# RX.net
KiCad netlist of a schematic drawn in Altium Designer
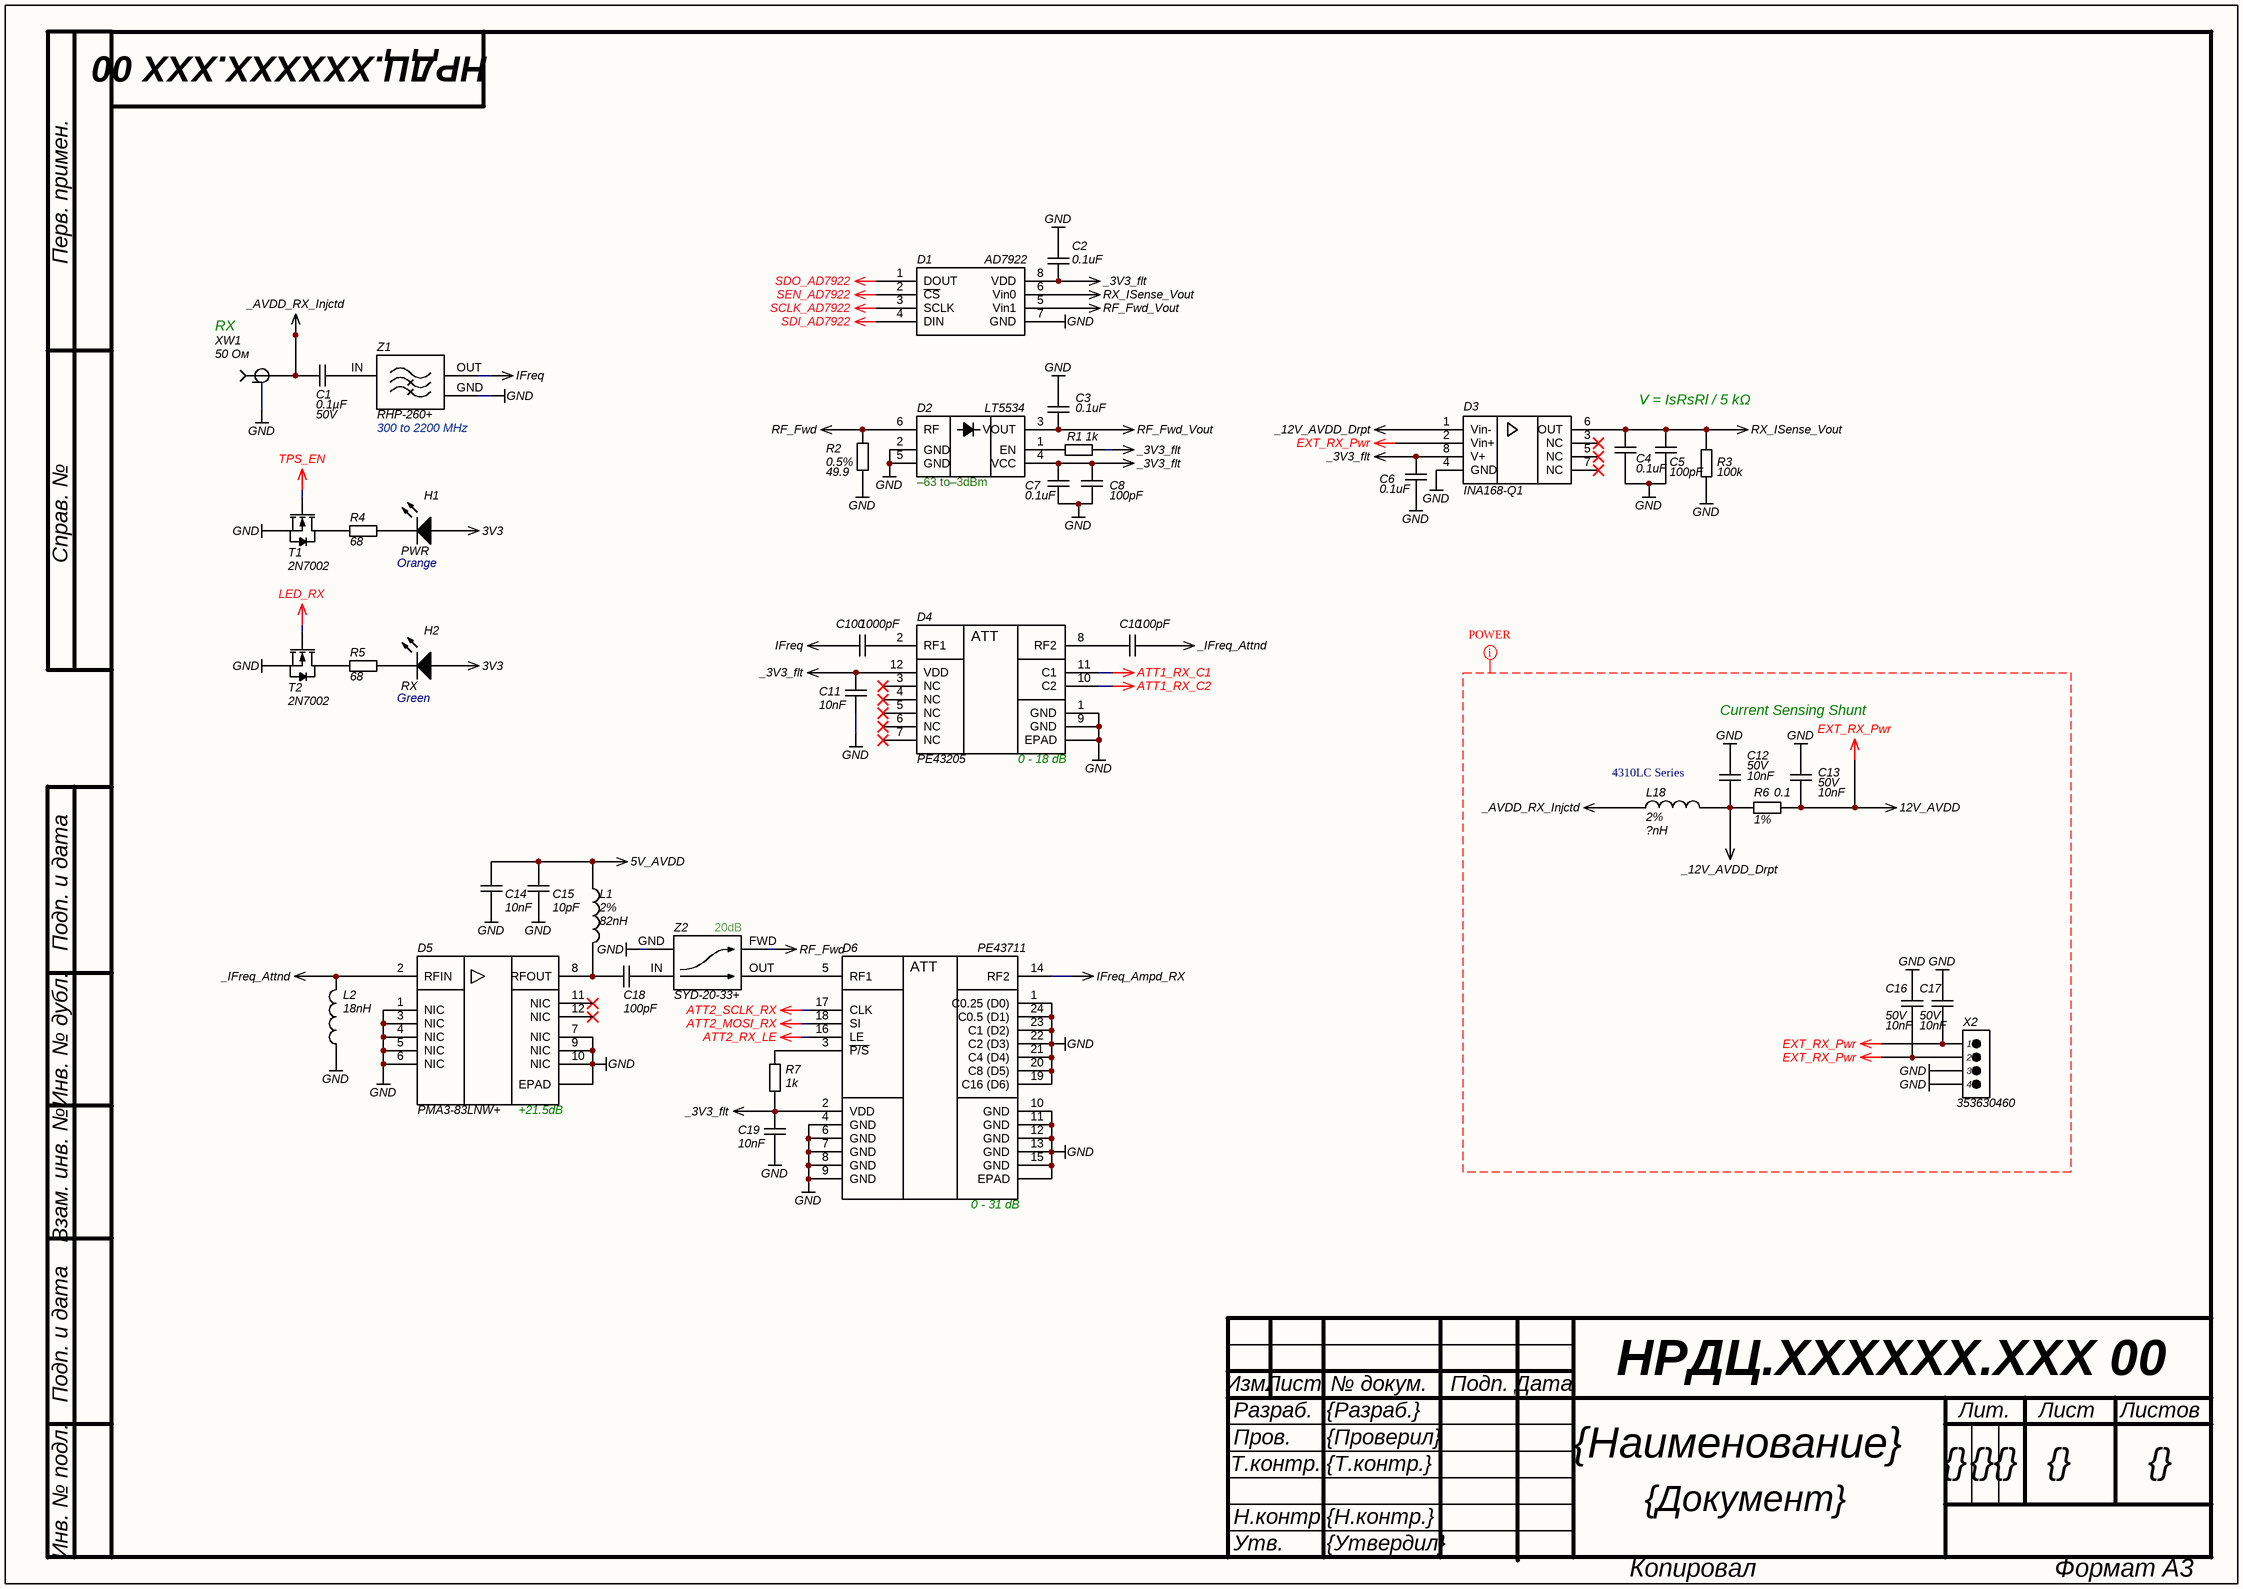
[diagram p0: RX.SchDoc]

(export (version "E")
  (design (tool "Eeschema 10.0.6"))
  (components
    (comp (ref "C1")
      (value "0.1µF")
      (footprint "C1206")
      (description "SMD Capacitor")
      (fields
        (field (name "MANUFACTURER") "Murata")
        (field (name "TOLERANCE") "5%")
        (field (name "VOLTAGE") "50V")
      )
      (libsource (lib "Kintex_SDR") (part "CAP"))
    )
    (comp (ref "C2")
      (value "0.1uF")
      (footprint "C0402")
      (description "SMD Capacitor")
      (fields (field (name "MANUFACTURER") "Murata") (field (name "TOLERANCE") "10%"))
      (libsource (lib "Kintex_SDR") (part "CAP"))
    )
    (comp (ref "C3")
      (value "0.1uF")
      (footprint "C0402")
      (description "SMD Capacitor")
      (fields (field (name "MANUFACTURER") "Murata") (field (name "TOLERANCE") "10%"))
      (libsource (lib "Kintex_SDR") (part "CAP"))
    )
    (comp (ref "C4")
      (value "0.1uF")
      (footprint "C0402")
      (description "SMD Capacitor")
      (fields (field (name "MANUFACTURER") "Murata") (field (name "TOLERANCE") "10%"))
      (libsource (lib "Kintex_SDR") (part "CAP"))
    )
    (comp (ref "C5")
      (value "100pF")
      (footprint "C0402")
      (description "SMD Capacitor")
      (fields (field (name "MANUFACTURER") "Murata") (field (name "TOLERANCE") "1%"))
      (libsource (lib "Kintex_SDR") (part "CAP"))
    )
    (comp (ref "C6")
      (value "0.1uF")
      (footprint "C0402")
      (description "SMD Capacitor")
      (fields (field (name "MANUFACTURER") "Murata") (field (name "TOLERANCE") "10%"))
      (libsource (lib "Kintex_SDR") (part "CAP"))
    )
    (comp (ref "C7")
      (value "0.1uF")
      (footprint "C0402")
      (description "SMD Capacitor")
      (fields (field (name "MANUFACTURER") "Murata") (field (name "TOLERANCE") "10%"))
      (libsource (lib "Kintex_SDR") (part "CAP"))
    )
    (comp (ref "C8")
      (value "100pF")
      (footprint "C0402")
      (description "SMD Capacitor")
      (fields (field (name "MANUFACTURER") "Murata") (field (name "TOLERANCE") "1%"))
      (libsource (lib "Kintex_SDR") (part "CAP"))
    )
    (comp (ref "C10")
      (value "100pF")
      (footprint "C0402")
      (description "SMD Capacitor")
      (fields (field (name "MANUFACTURER") "Murata") (field (name "TOLERANCE") "1%"))
      (libsource (lib "Kintex_SDR") (part "CAP"))
    )
    (comp (ref "C11")
      (value "10nF")
      (footprint "C0402")
      (description "SMD Capacitor")
      (fields (field (name "MANUFACTURER") "Murata") (field (name "TOLERANCE") "10%"))
      (libsource (lib "Kintex_SDR") (part "CAP"))
    )
    (comp (ref "C12")
      (value "10nF")
      (footprint "C0402")
      (description "SMD Capacitor")
      (fields
        (field (name "MANUFACTURER") "Murata")
        (field (name "TOLERANCE") "5%")
        (field (name "VOLTAGE") "50V")
      )
      (libsource (lib "Kintex_SDR") (part "CAP"))
    )
    (comp (ref "C13")
      (value "10nF")
      (footprint "C0402")
      (description "SMD Capacitor")
      (fields
        (field (name "MANUFACTURER") "Murata")
        (field (name "TOLERANCE") "5%")
        (field (name "VOLTAGE") "50V")
      )
      (libsource (lib "Kintex_SDR") (part "CAP"))
    )
    (comp (ref "C14")
      (value "10nF")
      (footprint "C0402")
      (description "SMD Capacitor")
      (fields (field (name "MANUFACTURER") "Murata") (field (name "TOLERANCE") "10%"))
      (libsource (lib "Kintex_SDR") (part "CAP"))
    )
    (comp (ref "C15")
      (value "10pF")
      (footprint "C0402")
      (description "SMD Capacitor")
      (fields (field (name "MANUFACTURER") "Murata") (field (name "TOLERANCE") "1%"))
      (libsource (lib "Kintex_SDR") (part "CAP"))
    )
    (comp (ref "C16")
      (value "10nF")
      (footprint "C0402")
      (description "SMD Capacitor")
      (fields
        (field (name "MANUFACTURER") "Murata")
        (field (name "TOLERANCE") "5%")
        (field (name "VOLTAGE") "50V")
      )
      (libsource (lib "Kintex_SDR") (part "CAP"))
    )
    (comp (ref "C17")
      (value "10nF")
      (footprint "C0402")
      (description "SMD Capacitor")
      (fields
        (field (name "MANUFACTURER") "Murata")
        (field (name "TOLERANCE") "5%")
        (field (name "VOLTAGE") "50V")
      )
      (libsource (lib "Kintex_SDR") (part "CAP"))
    )
    (comp (ref "C18")
      (value "100pF")
      (footprint "C0402")
      (description "SMD Capacitor")
      (fields (field (name "MANUFACTURER") "Murata") (field (name "TOLERANCE") "1%"))
      (libsource (lib "Kintex_SDR") (part "CAP"))
    )
    (comp (ref "C19")
      (value "10nF")
      (footprint "C0402")
      (description "SMD Capacitor")
      (fields (field (name "MANUFACTURER") "Murata") (field (name "TOLERANCE") "10%"))
      (libsource (lib "Kintex_SDR") (part "CAP"))
    )
    (comp (ref "C100")
      (value "1000pF")
      (footprint "C0402")
      (description "SMD Capacitor")
      (fields (field (name "MANUFACTURER") "Murata") (field (name "TOLERANCE") "5%"))
      (libsource (lib "Kintex_SDR") (part "CAP"))
    )
    (comp (ref "D1")
      (value "AD7922")
      (footprint "MSOP-8")
      (description "1 MSPS, 10-/12-Bit ADC")
      (fields (field (name "MANUFACTURER") "Analog Device") (field (name "VOLTAGE") "2.35 V to 5.25 V"))
      (libsource (lib "Kintex_SDR") (part "AD79x2"))
    )
    (comp (ref "D2")
      (value "LT5534")
      (footprint "DBLib:SC70")
      (description "50MHz to 3GHz monolithic RF power\r\ndetector")
      (fields
        (field (name "MANUFACTURER") "Linear Technology")
        (field (name "VOLTAGE") "Single 2.7V to 5.25V")
        (field (name "RF INPUT POWER RANGE") "–63 to–3dBm")
      )
      (libsource (lib "DBLib") (part "LT5534"))
    )
    (comp (ref "D3")
      (value "INA168-Q1")
      (footprint "DBLib:TSSOP (8)")
      (description "Automotive-Grade, High-Side, Current-Output, Current-Shunt Monitor")
      (fields (field (name "MANUFACTURER") "Texas Instruments") (field (name "VOLTAGE") "2.7 V to 60 V"))
      (libsource (lib "DBLib") (part "INA168-Q1"))
    )
    (comp (ref "D4")
      (value "PE43205")
      (footprint "DBLib:QFN-12")
      (description "50Ω, HaRP™ technology-enhanced\r\nfast switching 2-bit RF Digital Step Attenuator")
      (fields (field (name "MANUFACTURER") "Peregrine Technical Solutions"))
      (libsource (lib "DBLib") (part "PE43205"))
    )
    (comp (ref "D5")
      (value "PMA3-83LNW+")
      (footprint "DQ1225")
      (description "PHEMT based wideband, low noise MMIC amplifier")
      (fields (field (name "MANUFACTURER") "Mini-Circuits"))
      (libsource (lib "DBLib") (part "PMA3-83LNW+"))
    )
    (comp (ref "D6")
      (value "PE43711")
      (footprint "QFN-24")
      (description "The PE43711 is a 50Ω, HaRP™ technology-enhanced, 7-bit RF digital step attenuator")
      (fields (field (name "MANUFACTURER") "Peregrine Technical Solutions"))
      (libsource (lib "DBLib") (part "PE43711"))
    )
    (comp (ref "H1")
      (value "PWR")
      (footprint "LED_0805_Green")
      (description "CHIP LED LAMP")
      (fields (field (name "MANUFACTURER") "Kingbright") (field (name "COLOR") "Green"))
      (libsource (lib "DBLib") (part "LED"))
    )
    (comp (ref "H2")
      (value "RX")
      (footprint "LED_0805_Green")
      (description "CHIP LED LAMP")
      (fields (field (name "MANUFACTURER") "Kingbright") (field (name "COLOR") "Orange"))
      (libsource (lib "DBLib") (part "LED"))
    )
    (comp (ref "L1")
      (value "82nH")
      (footprint "DBLib:L0603_HP")
      (description "Chip SMD Inductor")
      (fields
        (field (name "MANUFACTURER") "Coilcraft")
        (field (name "TOLERANCE") "2%")
        (field (name "Comment") "Inductor RF")
      )
      (libsource (lib "") (part "Inductor RF_1"))
    )
    (comp (ref "L2")
      (value "18nH")
      (footprint "DBLib:L0603_HP")
      (description "Chip SMD Inductor")
      (fields (field (name "MANUFACTURER") "Coilcraft") (field (name "TOLERANCE") "5%"))
      (libsource (lib "DBLib") (part "Inductor RF"))
    )
    (comp (ref "L18")
      (value "?nH")
      (footprint "DBLib:4310LC")
      (description "Chip SMD Inductor")
      (fields
        (field (name "MANUFACTURER") "Coilcraft")
        (field (name "TOLERANCE") "2%")
        (field (name "Comment") "Inductor RF")
      )
      (libsource (lib "") (part "Inductor RF_1"))
    )
    (comp (ref "R1")
      (value "1k")
      (footprint "R0402")
      (description "SMD Resistor")
      (fields (field (name "POWER") "0.062 Wt") (field (name "TOLERANCE") "5%"))
      (libsource (lib "Kintex_SDR") (part "RES"))
    )
    (comp (ref "R2")
      (value "49.9")
      (footprint "R0402")
      (description "SMD Resistor")
      (fields
        (field (name "POWER") "0.063 Wt")
        (field (name "TOLERANCE") "0.5%")
        (field (name "MANUFACTURER") "Panasonic Electronic Components")
      )
      (libsource (lib "") (part "RES_1"))
    )
    (comp (ref "R3")
      (value "100k")
      (footprint "R0402")
      (description "SMD Resistor")
      (fields (field (name "POWER") "1/5 Wt") (field (name "TOLERANCE") "1%"))
      (libsource (lib "") (part "RES_3"))
    )
    (comp (ref "R4")
      (value "68")
      (footprint "R0402")
      (description "SMD Resistor")
      (fields (field (name "POWER") "0.062 Wt") (field (name "TOLERANCE") "5%"))
      (libsource (lib "") (part "RES_2"))
    )
    (comp (ref "R5")
      (value "68")
      (footprint "R0402")
      (description "SMD Resistor")
      (fields (field (name "POWER") "0.062 Wt") (field (name "TOLERANCE") "5%"))
      (libsource (lib "Kintex_SDR") (part "RES"))
    )
    (comp (ref "R6")
      (value "0.1")
      (footprint "R0805")
      (description "SMD Resistor")
      (fields
        (field (name "POWER") "1/2 Wt")
        (field (name "TOLERANCE") "1%")
        (field (name "MANUFACTURER") "Panasonic Electronic Components")
      )
      (libsource (lib "Kintex_SDR") (part "RES"))
    )
    (comp (ref "R7")
      (value "1k")
      (footprint "R0402")
      (description "SMD Resistor")
      (fields (field (name "POWER") "0.062 Wt") (field (name "TOLERANCE") "5%"))
      (libsource (lib "") (part "RES_3"))
    )
    (comp (ref "T1")
      (value "2N7002")
      (footprint "SOT-23")
      (description "N-Channel MOSFET 2N7002")
      (fields (field (name "VOLTAGE") "60V"))
      (libsource (lib "Kintex_SDR") (part "2N7002"))
    )
    (comp (ref "T2")
      (value "2N7002")
      (footprint "SOT-23")
      (description "N-Channel MOSFET 2N7002")
      (fields (field (name "VOLTAGE") "60V"))
      (libsource (lib "Kintex_SDR") (part "2N7002"))
    )
    (comp (ref "X2")
      (value "353630460")
      (footprint "DBLib:CON_353630460")
      (description "2.00mm Pitch Sherlock Wire-to-Board Header, Right-Angle, with Positive Lock, 4 Circuits")
      (fields (field (name "MANUFACTURER") "Molex"))
      (libsource (lib "DBLib") (part "353630460"))
    )
    (comp (ref "XW1")
      (value "50 Ом")
      (footprint "MOLEX SD-73251-135 (Gold)")
      (description "50 Ohms, SMA Jack, Vertica")
      (fields (field (name "MANUFACTURER") "Molex"))
      (libsource (lib "DBLib") (part "RF Connector"))
    )
    (comp (ref "Z1")
      (value "RHP-260+")
      (footprint "GP731")
      (description "High Pass Filter")
      (fields (field (name "MANUFACTURER") "Mini-Circuits") (field (name "FREQUENCY") "300 to 2200 MHz"))
      (libsource (lib "DBLib") (part "RHP-260+"))
    )
    (comp (ref "Z2")
      (value "SYD-20-33+")
      (footprint "DBLib:AH202")
      (description "Directional Coupler")
      (fields (field (name "MANUFACTURER") "Mini-Circuits") (field (name "COUPLING") "20dB"))
      (libsource (lib "DBLib") (part "SYD-20-33+"))
    )
  )
  (nets
    (net (code "1") (name "3V3") (class "Default")
      (node (ref "H1") (pin "2") (pinfunction "A_2") (pintype "passive"))
      (node (ref "H2") (pin "2") (pinfunction "A_2") (pintype "passive"))
    )
    (net (code "2") (name "5V_AVDD") (class "Default")
      (node (ref "C14") (pin "2") (pinfunction "2_2") (pintype "passive"))
      (node (ref "C15") (pin "2") (pinfunction "2_2") (pintype "passive"))
      (node (ref "L1") (pin "2") (pinfunction "2_2") (pintype "passive"))
    )
    (net (code "3") (name "12V_AVDD") (class "Default")
      (node (ref "C13") (pin "1") (pinfunction "1_1") (pintype "passive"))
      (node (ref "C16") (pin "2") (pinfunction "2_2") (pintype "passive"))
      (node (ref "C17") (pin "2") (pinfunction "2_2") (pintype "passive"))
      (node (ref "D3") (pin "2") (pinfunction "Vin+_2") (pintype "passive"))
      (node (ref "R6") (pin "1") (pinfunction "1_1") (pintype "passive"))
      (node (ref "X2") (pin "1") (pinfunction "1_1") (pintype "passive"))
      (node (ref "X2") (pin "2") (pinfunction "2_2") (pintype "passive"))
    )
    (net (code "4") (name "ATT1_RX_C1") (class "Default")
      (node (ref "D4") (pin "11") (pinfunction "C1_11") (pintype "passive"))
    )
    (net (code "5") (name "ATT1_RX_C2") (class "Default")
      (node (ref "D4") (pin "10") (pinfunction "C2_10") (pintype "passive"))
    )
    (net (code "6") (name "ATT2_MOSI_RX") (class "Default")
      (node (ref "D6") (pin "18") (pinfunction "SI_18") (pintype "passive"))
    )
    (net (code "7") (name "ATT2_RX_LE") (class "Default")
      (node (ref "D6") (pin "16") (pinfunction "LE_16") (pintype "passive"))
    )
    (net (code "8") (name "ATT2_SCLK_RX") (class "Default")
      (node (ref "D6") (pin "17") (pinfunction "CLK_17") (pintype "passive"))
    )
    (net (code "9") (name "GND") (class "Default")
      (node (ref "C11") (pin "1") (pinfunction "1_1") (pintype "passive"))
      (node (ref "C12") (pin "2") (pinfunction "2_2") (pintype "passive"))
      (node (ref "C13") (pin "2") (pinfunction "2_2") (pintype "passive"))
      (node (ref "C14") (pin "1") (pinfunction "1_1") (pintype "passive"))
      (node (ref "C15") (pin "1") (pinfunction "1_1") (pintype "passive"))
      (node (ref "C16") (pin "1") (pinfunction "1_1") (pintype "passive"))
      (node (ref "C17") (pin "1") (pinfunction "1_1") (pintype "passive"))
      (node (ref "C19") (pin "1") (pinfunction "1_1") (pintype "passive"))
      (node (ref "C2") (pin "2") (pinfunction "2_2") (pintype "passive"))
      (node (ref "C3") (pin "1") (pinfunction "1_1") (pintype "passive"))
      (node (ref "C4") (pin "1") (pinfunction "1_1") (pintype "passive"))
      (node (ref "C5") (pin "1") (pinfunction "1_1") (pintype "passive"))
      (node (ref "C6") (pin "1") (pinfunction "1_1") (pintype "passive"))
      (node (ref "C7") (pin "1") (pinfunction "1_1") (pintype "passive"))
      (node (ref "C8") (pin "1") (pinfunction "1_1") (pintype "passive"))
      (node (ref "D1") (pin "7") (pinfunction "GND_7") (pintype "passive"))
      (node (ref "D2") (pin "2") (pinfunction "GND_2") (pintype "passive"))
      (node (ref "D2") (pin "5") (pinfunction "GND_5") (pintype "passive"))
      (node (ref "D3") (pin "4") (pinfunction "GND_4") (pintype "passive"))
      (node (ref "D4") (pin "1") (pinfunction "GND_1") (pintype "passive"))
      (node (ref "D4") (pin "13") (pinfunction "EPAD_13") (pintype "passive"))
      (node (ref "D4") (pin "9") (pinfunction "GND_9") (pintype "passive"))
      (node (ref "D5") (pin "1") (pinfunction "NIC_1") (pintype "passive"))
      (node (ref "D5") (pin "10") (pinfunction "NIC_10") (pintype "passive"))
      (node (ref "D5") (pin "13") (pinfunction "EPAD_13") (pintype "passive"))
      (node (ref "D5") (pin "3") (pinfunction "NIC_3") (pintype "passive"))
      (node (ref "D5") (pin "4") (pinfunction "NIC_4") (pintype "passive"))
      (node (ref "D5") (pin "5") (pinfunction "NIC_5") (pintype "passive"))
      (node (ref "D5") (pin "6") (pinfunction "NIC_6") (pintype "passive"))
      (node (ref "D5") (pin "7") (pinfunction "NIC_7") (pintype "passive"))
      (node (ref "D5") (pin "9") (pinfunction "NIC_9") (pintype "passive"))
      (node (ref "D6") (pin "1") (pinfunction "C0.25_(D0)_1") (pintype "passive"))
      (node (ref "D6") (pin "10") (pinfunction "GND_10") (pintype "passive"))
      (node (ref "D6") (pin "11") (pinfunction "GND_11") (pintype "passive"))
      (node (ref "D6") (pin "12") (pinfunction "GND_12") (pintype "passive"))
      (node (ref "D6") (pin "13") (pinfunction "GND_13") (pintype "passive"))
      (node (ref "D6") (pin "15") (pinfunction "GND_15") (pintype "passive"))
      (node (ref "D6") (pin "19") (pinfunction "C16_(D6)_19") (pintype "passive"))
      (node (ref "D6") (pin "20") (pinfunction "C8_(D5)_20") (pintype "passive"))
      (node (ref "D6") (pin "21") (pinfunction "C4_(D4)_21") (pintype "passive"))
      (node (ref "D6") (pin "22") (pinfunction "C2_(D3)_22") (pintype "passive"))
      (node (ref "D6") (pin "23") (pinfunction "C1_(D2)_23") (pintype "passive"))
      (node (ref "D6") (pin "24") (pinfunction "C0.5_(D1)_24") (pintype "passive"))
      (node (ref "D6") (pin "25") (pinfunction "EPAD_25") (pintype "passive"))
      (node (ref "D6") (pin "4") (pinfunction "GND_4") (pintype "passive"))
      (node (ref "D6") (pin "6") (pinfunction "GND_6") (pintype "passive"))
      (node (ref "D6") (pin "7") (pinfunction "GND_7") (pintype "passive"))
      (node (ref "D6") (pin "8") (pinfunction "GND_8") (pintype "passive"))
      (node (ref "D6") (pin "9") (pinfunction "GND_9") (pintype "passive"))
      (node (ref "L2") (pin "1") (pinfunction "1_1") (pintype "passive"))
      (node (ref "R2") (pin "2") (pinfunction "2_2") (pintype "passive"))
      (node (ref "R3") (pin "1") (pinfunction "1_1") (pintype "passive"))
      (node (ref "T1") (pin "2") (pinfunction "S_2") (pintype "passive"))
      (node (ref "T2") (pin "2") (pinfunction "S_2") (pintype "passive"))
      (node (ref "X2") (pin "3") (pinfunction "3_3") (pintype "passive"))
      (node (ref "X2") (pin "4") (pinfunction "4_4") (pintype "passive"))
      (node (ref "XW1") (pin "G") (pinfunction "GND_G") (pintype "passive"))
      (node (ref "Z1") (pin "GND") (pinfunction "GND_GND") (pintype "passive"))
      (node (ref "Z2") (pin "GND") (pinfunction "GND_GND") (pintype "passive"))
    )
    (net (code "10") (name "IFreq") (class "Default")
      (node (ref "C100") (pin "1") (pinfunction "1_1") (pintype "passive"))
      (node (ref "Z1") (pin "OUT") (pinfunction "OUT_OUT") (pintype "passive"))
    )
    (net (code "11") (name "IFreq_Ampd_RX") (class "Default")
      (node (ref "D6") (pin "14") (pinfunction "RF2_14") (pintype "passive"))
    )
    (net (code "12") (name "LED_RX") (class "Default")
      (node (ref "T2") (pin "1") (pinfunction "G_1") (pintype "passive"))
    )
    (net (code "13") (name "Net-(C1-Pad2)") (class "Default")
      (node (ref "C1") (pin "2") (pinfunction "2_2") (pintype "passive"))
      (node (ref "Z1") (pin "IN") (pinfunction "IN_IN") (pintype "passive"))
    )
    (net (code "14") (name "Net-(C18-Pad2)") (class "Default")
      (node (ref "C18") (pin "2") (pinfunction "2_2") (pintype "passive"))
      (node (ref "Z2") (pin "IN") (pinfunction "IN_IN") (pintype "passive"))
    )
    (net (code "15") (name "Net-(D2-EN)") (class "Default")
      (node (ref "D2") (pin "1") (pinfunction "EN_1") (pintype "passive"))
      (node (ref "R1") (pin "2") (pinfunction "2_2") (pintype "passive"))
    )
    (net (code "16") (name "Net-(D4-RF1)") (class "Default")
      (node (ref "C100") (pin "2") (pinfunction "2_2") (pintype "passive"))
      (node (ref "D4") (pin "2") (pinfunction "RF1_2") (pintype "passive"))
    )
    (net (code "17") (name "Net-(D4-RF2)") (class "Default")
      (node (ref "C10") (pin "1") (pinfunction "1_1") (pintype "passive"))
      (node (ref "D4") (pin "8") (pinfunction "RF2_8") (pintype "passive"))
    )
    (net (code "18") (name "Net-(D5-RFOUT)") (class "Default")
      (node (ref "C18") (pin "1") (pinfunction "1_1") (pintype "passive"))
      (node (ref "D5") (pin "8") (pinfunction "RFOUT_8") (pintype "passive"))
      (node (ref "L1") (pin "1") (pinfunction "1_1") (pintype "passive"))
    )
    (net (code "19") (name "Net-(D6-RF1)") (class "Default")
      (node (ref "D6") (pin "5") (pinfunction "RF1_5") (pintype "passive"))
      (node (ref "Z2") (pin "OUT") (pinfunction "OUT_OUT") (pintype "passive"))
    )
    (net (code "20") (name "Net-(D6-~{P{slash}S})") (class "Default")
      (node (ref "D6") (pin "3") (pinfunction "~{P/S}_3") (pintype "passive"))
      (node (ref "R7") (pin "2") (pinfunction "2_2") (pintype "passive"))
    )
    (net (code "21") (name "Net-(H1-K)") (class "Default")
      (node (ref "H1") (pin "1") (pinfunction "K_1") (pintype "passive"))
      (node (ref "R4") (pin "2") (pinfunction "2_2") (pintype "passive"))
    )
    (net (code "22") (name "Net-(H2-K)") (class "Default")
      (node (ref "H2") (pin "1") (pinfunction "K_1") (pintype "passive"))
      (node (ref "R5") (pin "1") (pinfunction "1_1") (pintype "passive"))
    )
    (net (code "23") (name "Net-(T1-D)") (class "Default")
      (node (ref "R4") (pin "1") (pinfunction "1_1") (pintype "passive"))
      (node (ref "T1") (pin "3") (pinfunction "D_3") (pintype "passive"))
    )
    (net (code "24") (name "Net-(T2-D)") (class "Default")
      (node (ref "R5") (pin "2") (pinfunction "2_2") (pintype "passive"))
      (node (ref "T2") (pin "3") (pinfunction "D_3") (pintype "passive"))
    )
    (net (code "25") (name "RF_Fwd") (class "Default")
      (node (ref "D2") (pin "6") (pinfunction "RF_6") (pintype "passive"))
      (node (ref "R2") (pin "1") (pinfunction "1_1") (pintype "passive"))
      (node (ref "Z2") (pin "FWD") (pinfunction "FWD_FWD") (pintype "passive"))
    )
    (net (code "26") (name "RF_Fwd_Vout") (class "Default")
      (node (ref "C3") (pin "2") (pinfunction "2_2") (pintype "passive"))
      (node (ref "D1") (pin "5") (pinfunction "Vin1_5") (pintype "passive"))
      (node (ref "D2") (pin "3") (pinfunction "VOUT_3") (pintype "passive"))
    )
    (net (code "27") (name "RX_ISense_Vout") (class "Default")
      (node (ref "C4") (pin "2") (pinfunction "2_2") (pintype "passive"))
      (node (ref "C5") (pin "2") (pinfunction "2_2") (pintype "passive"))
      (node (ref "D1") (pin "6") (pinfunction "Vin0_6") (pintype "passive"))
      (node (ref "D3") (pin "6") (pinfunction "OUT_6") (pintype "passive"))
      (node (ref "R3") (pin "2") (pinfunction "2_2") (pintype "passive"))
    )
    (net (code "28") (name "SCLK_AD7922") (class "Default")
      (node (ref "D1") (pin "3") (pinfunction "SCLK_3") (pintype "passive"))
    )
    (net (code "29") (name "SDI_AD7922") (class "Default")
      (node (ref "D1") (pin "4") (pinfunction "DIN_4") (pintype "passive"))
    )
    (net (code "30") (name "SDO_AD7922") (class "Default")
      (node (ref "D1") (pin "1") (pinfunction "DOUT_1") (pintype "passive"))
    )
    (net (code "31") (name "SEN_AD7922") (class "Default")
      (node (ref "D1") (pin "2") (pinfunction "~{CS}_2") (pintype "passive"))
    )
    (net (code "32") (name "TPS_EN") (class "Default")
      (node (ref "T1") (pin "1") (pinfunction "G_1") (pintype "passive"))
    )
    (net (code "33") (name "_3V3_flt") (class "Default")
      (node (ref "C11") (pin "2") (pinfunction "2_2") (pintype "passive"))
      (node (ref "C19") (pin "2") (pinfunction "2_2") (pintype "passive"))
      (node (ref "C2") (pin "1") (pinfunction "1_1") (pintype "passive"))
      (node (ref "C6") (pin "2") (pinfunction "2_2") (pintype "passive"))
      (node (ref "C7") (pin "2") (pinfunction "2_2") (pintype "passive"))
      (node (ref "C8") (pin "2") (pinfunction "2_2") (pintype "passive"))
      (node (ref "D1") (pin "8") (pinfunction "VDD_8") (pintype "passive"))
      (node (ref "D2") (pin "4") (pinfunction "VCC_4") (pintype "passive"))
      (node (ref "D3") (pin "8") (pinfunction "V+_8") (pintype "passive"))
      (node (ref "D4") (pin "12") (pinfunction "VDD_12") (pintype "passive"))
      (node (ref "D6") (pin "2") (pinfunction "VDD_2") (pintype "passive"))
      (node (ref "R1") (pin "1") (pinfunction "1_1") (pintype "passive"))
      (node (ref "R7") (pin "1") (pinfunction "1_1") (pintype "passive"))
    )
    (net (code "34") (name "_12V_AVDD_Drpt") (class "Default")
      (node (ref "C12") (pin "1") (pinfunction "1_1") (pintype "passive"))
      (node (ref "D3") (pin "1") (pinfunction "Vin-_1") (pintype "passive"))
      (node (ref "L18") (pin "1") (pinfunction "1_1") (pintype "passive"))
      (node (ref "R6") (pin "2") (pinfunction "2_2") (pintype "passive"))
    )
    (net (code "35") (name "_AVDD_RX_Injctd") (class "Default")
      (node (ref "C1") (pin "1") (pinfunction "1_1") (pintype "passive"))
      (node (ref "L18") (pin "2") (pinfunction "2_2") (pintype "passive"))
      (node (ref "XW1") (pin "S") (pinfunction "RF_S") (pintype "passive"))
    )
    (net (code "36") (name "_IFreq_Attnd") (class "Default")
      (node (ref "C10") (pin "2") (pinfunction "2_2") (pintype "passive"))
      (node (ref "D5") (pin "2") (pinfunction "RFIN_2") (pintype "passive"))
      (node (ref "L2") (pin "2") (pinfunction "2_2") (pintype "passive"))
    )
    (net (code "37") (name "unconnected-(D3-NC-Pad3)") (class "Default")
      (node (ref "D3") (pin "3") (pinfunction "NC_3") (pintype "passive+no_connect"))
    )
    (net (code "38") (name "unconnected-(D3-NC-Pad5)") (class "Default")
      (node (ref "D3") (pin "5") (pinfunction "NC_5") (pintype "passive+no_connect"))
    )
    (net (code "39") (name "unconnected-(D3-NC-Pad7)") (class "Default")
      (node (ref "D3") (pin "7") (pinfunction "NC_7") (pintype "passive+no_connect"))
    )
    (net (code "40") (name "unconnected-(D4-NC-Pad3)") (class "Default")
      (node (ref "D4") (pin "3") (pinfunction "NC_3") (pintype "passive+no_connect"))
    )
    (net (code "41") (name "unconnected-(D4-NC-Pad4)") (class "Default")
      (node (ref "D4") (pin "4") (pinfunction "NC_4") (pintype "passive+no_connect"))
    )
    (net (code "42") (name "unconnected-(D4-NC-Pad5)") (class "Default")
      (node (ref "D4") (pin "5") (pinfunction "NC_5") (pintype "passive+no_connect"))
    )
    (net (code "43") (name "unconnected-(D4-NC-Pad6)") (class "Default")
      (node (ref "D4") (pin "6") (pinfunction "NC_6") (pintype "passive+no_connect"))
    )
    (net (code "44") (name "unconnected-(D4-NC-Pad7)") (class "Default")
      (node (ref "D4") (pin "7") (pinfunction "NC_7") (pintype "passive+no_connect"))
    )
    (net (code "45") (name "unconnected-(D5-NIC-Pad11)") (class "Default")
      (node (ref "D5") (pin "11") (pinfunction "NIC_11") (pintype "passive+no_connect"))
    )
    (net (code "46") (name "unconnected-(D5-NIC-Pad12)") (class "Default")
      (node (ref "D5") (pin "12") (pinfunction "NIC_12") (pintype "passive+no_connect"))
    )
  )
)
